# U_I_Meter_TOP.net
KiCad netlist of a schematic drawn in Altium Designer
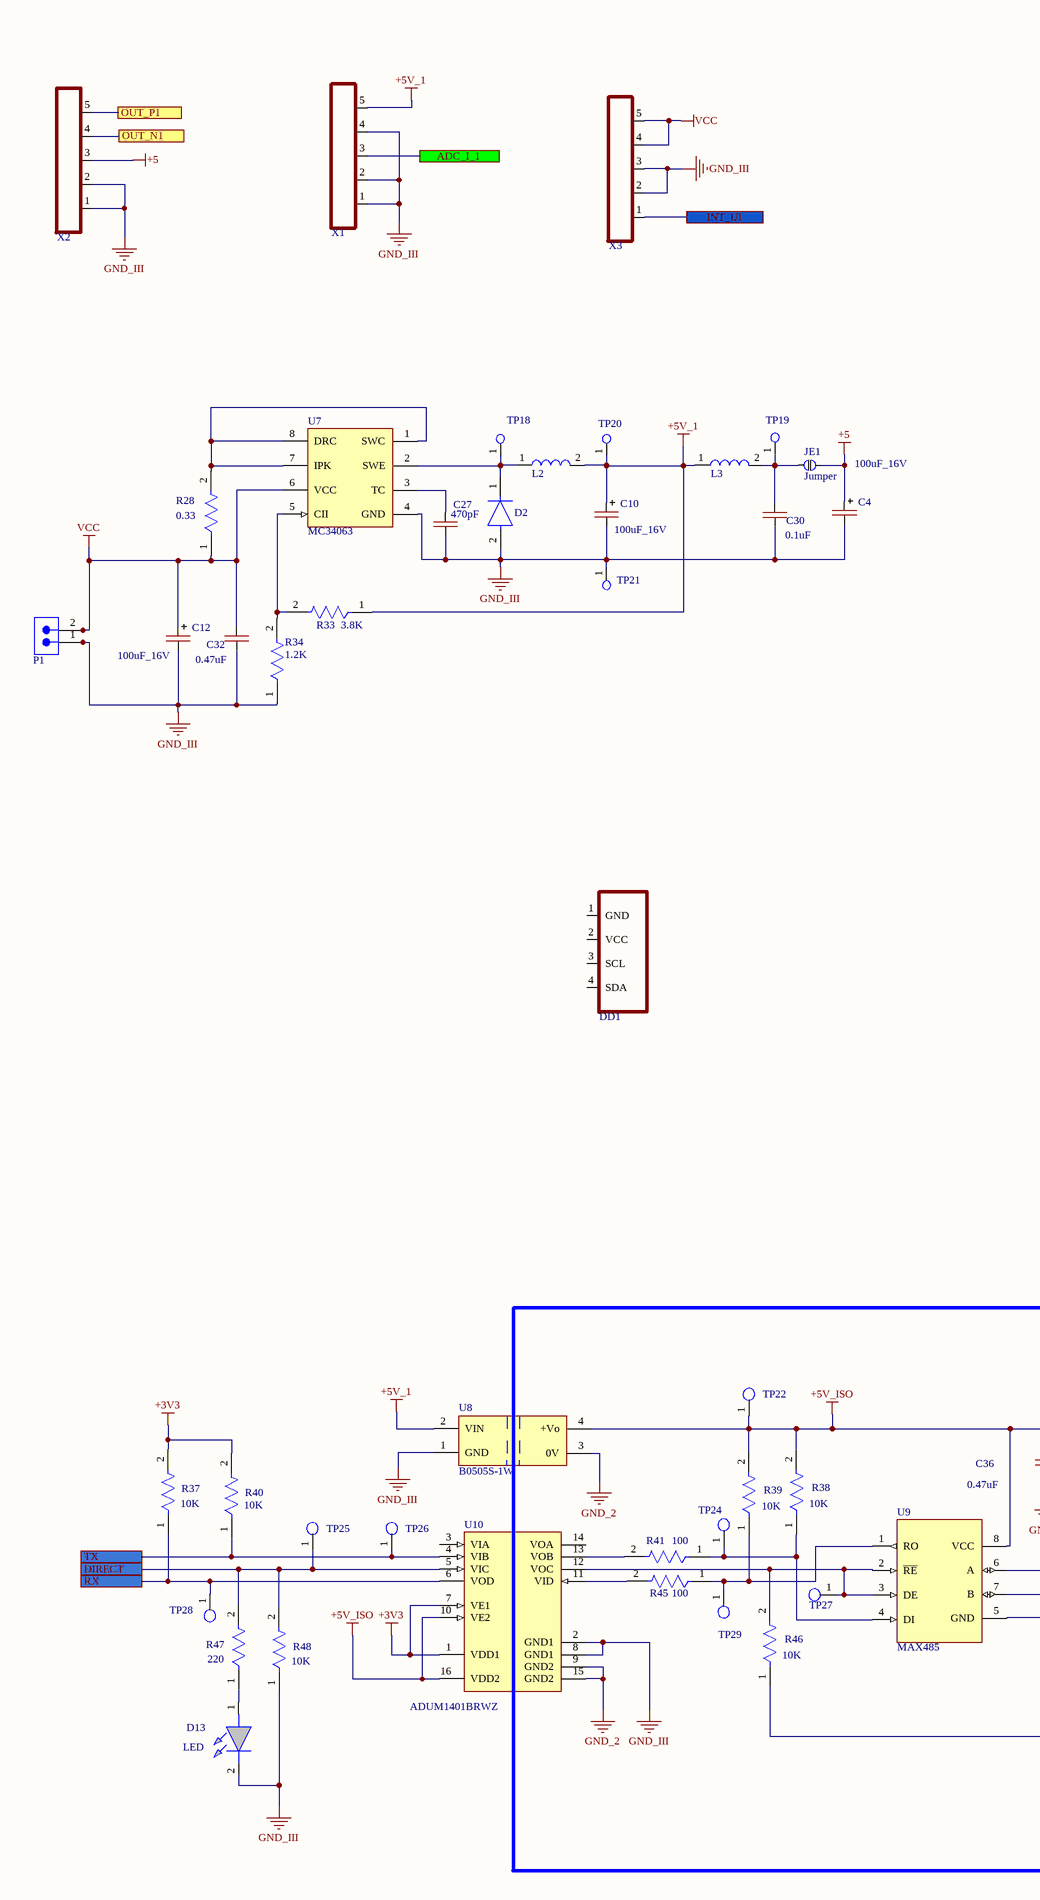
[diagram p0: U_I_Meter_TOP.SchDoc, left]
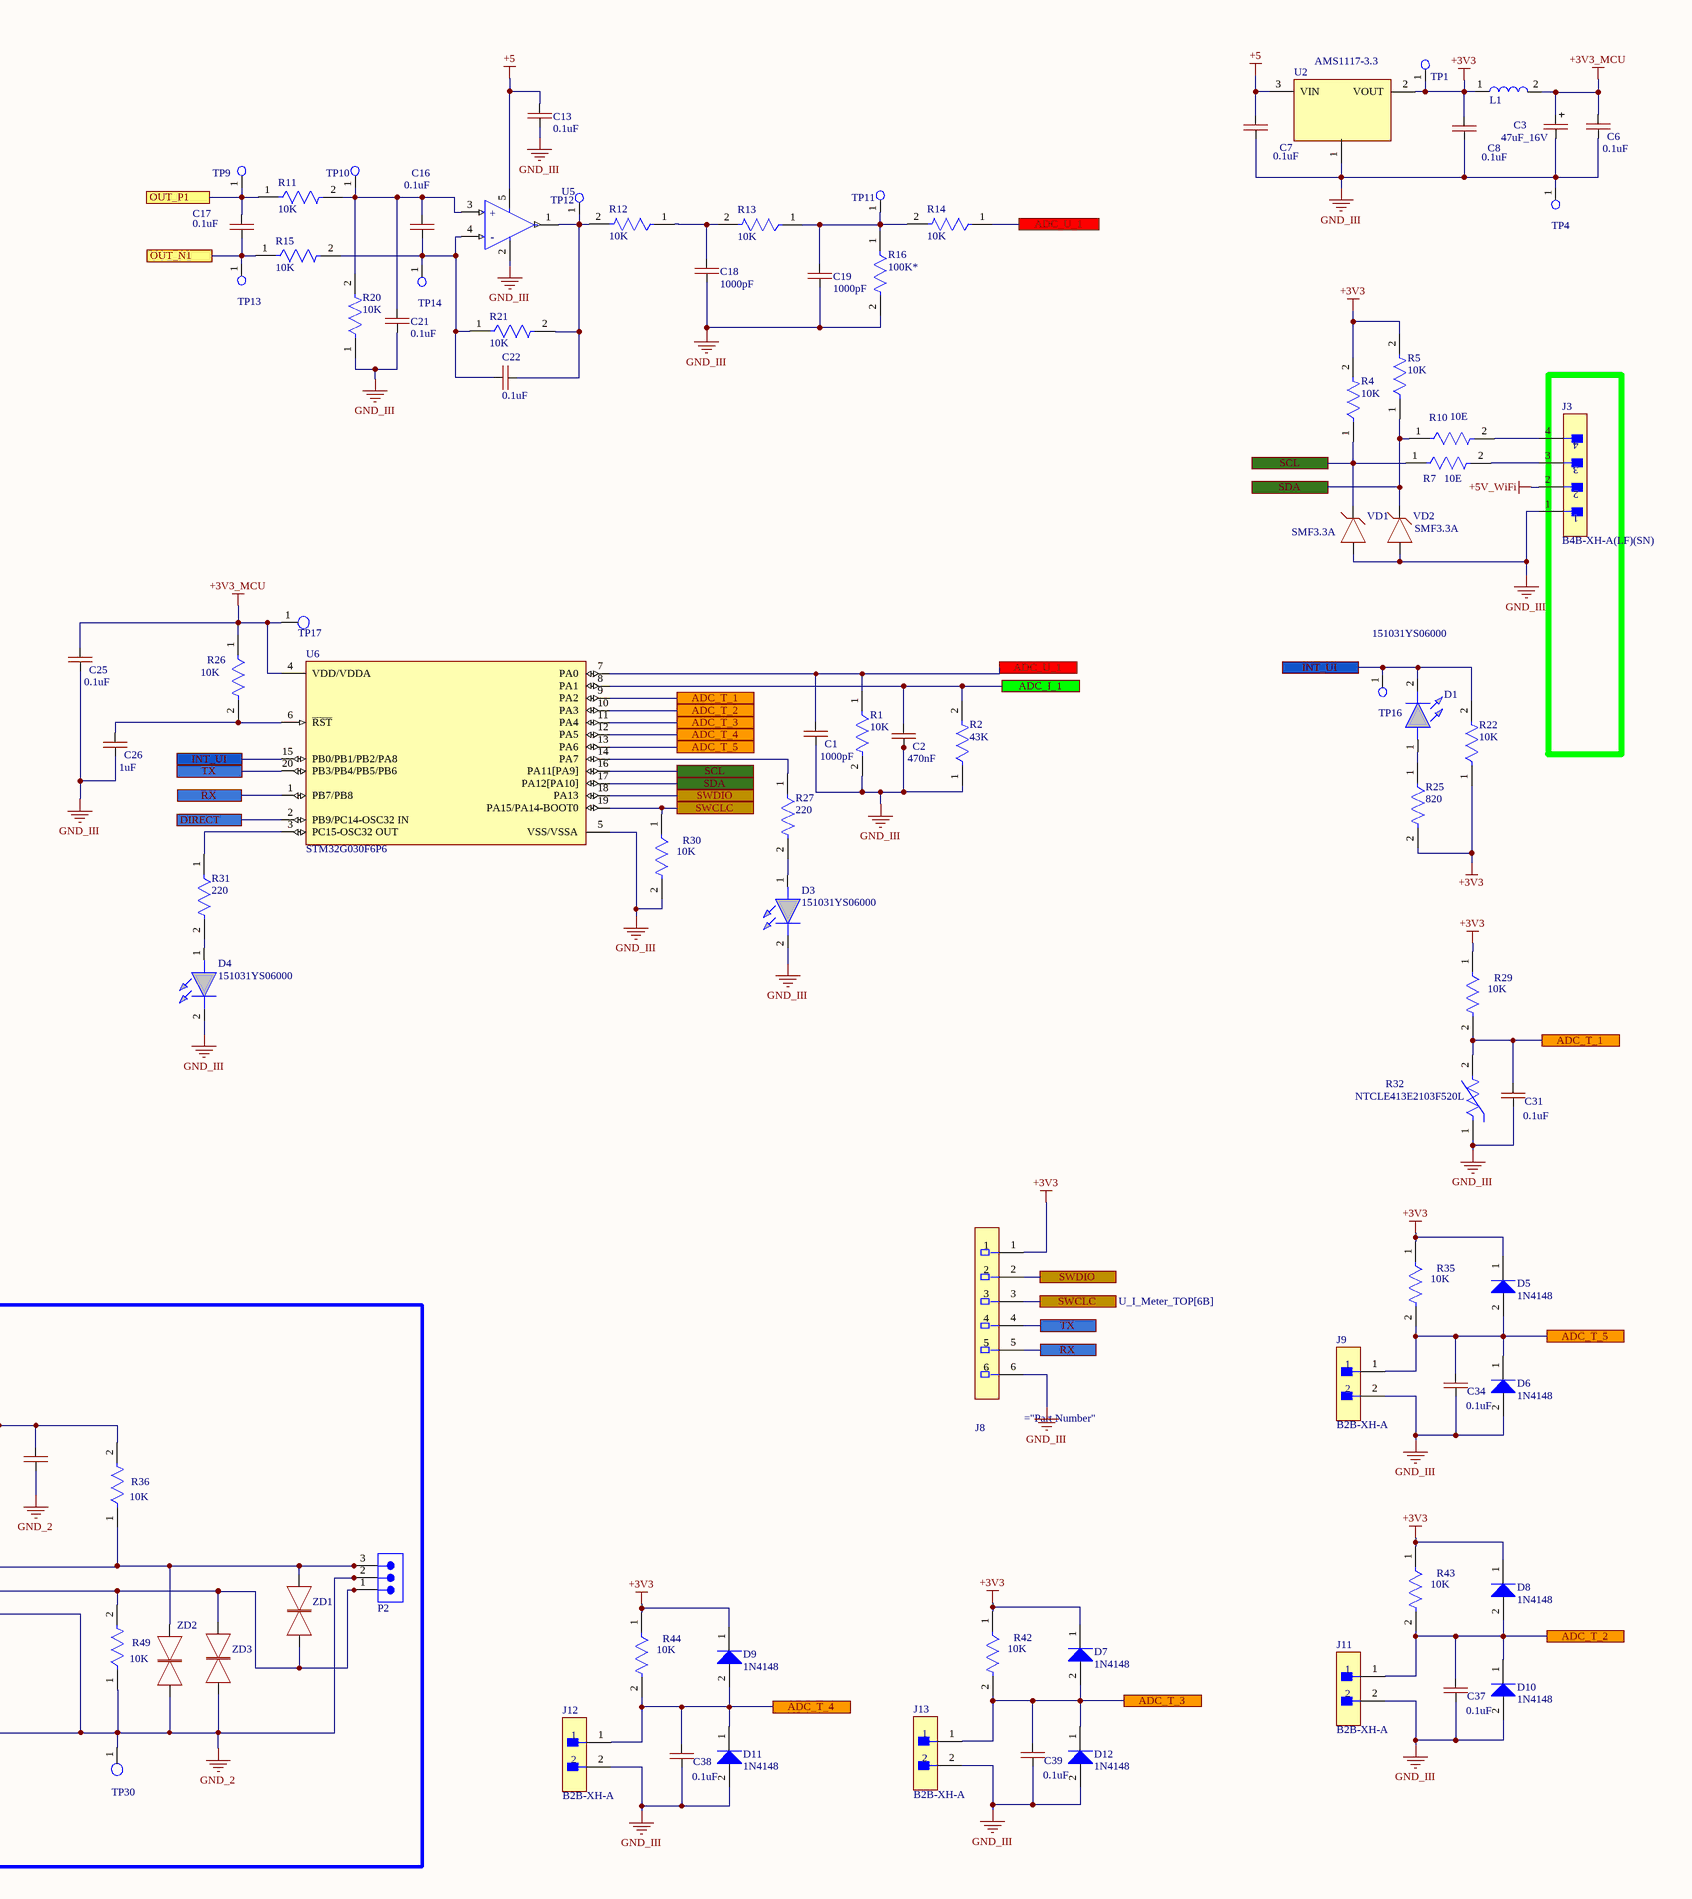
[diagram p1: U_I_Meter_TOP.SchDoc, right]

(export (version "E")
  (design (tool "Eeschema 10.0.6"))
  (components
    (comp (ref "C1")
      (value "1000pF")
      (footprint "CAP-0805")
      (libsource (lib "PASSIVE_COMPONENTS") (part "CAP-NON-POLAR"))
    )
    (comp (ref "C2")
      (value "470nF")
      (footprint "CAP-0805")
      (libsource (lib "PASSIVE_COMPONENTS") (part "CAP-NON-POLAR"))
    )
    (comp (ref "C3")
      (value "47uF_16V")
      (footprint "CAP-TAN-D")
      (libsource (lib "PASSIVE_COMPONENTS") (part "CAP-POLAR"))
    )
    (comp (ref "C4")
      (value "100uF_16V")
      (footprint "CAP-TAN-D")
      (libsource (lib "PASSIVE_COMPONENTS") (part "CAP_POL_SMD"))
    )
    (comp (ref "C6")
      (value "0.1uF")
      (footprint "CAP-0805")
      (libsource (lib "PASSIVE_COMPONENTS") (part "CAP-NON-POLAR"))
    )
    (comp (ref "C7")
      (value "0.1uF")
      (footprint "CAP-0805")
      (libsource (lib "PASSIVE_COMPONENTS") (part "CAP-NON-POLAR"))
    )
    (comp (ref "C8")
      (value "0.1uF")
      (footprint "CAP-0805")
      (libsource (lib "PASSIVE_COMPONENTS") (part "CAP-NON-POLAR"))
    )
    (comp (ref "C10")
      (value "100uF_16V")
      (footprint "CAP-TAN-D")
      (libsource (lib "PASSIVE_COMPONENTS") (part "CAP_POL_SMD"))
    )
    (comp (ref "C12")
      (value "100uF_16V")
      (footprint "CAP-TAN-D")
      (libsource (lib "PASSIVE_COMPONENTS") (part "CAP_POL_SMD"))
    )
    (comp (ref "C13")
      (value "0.1uF")
      (footprint "CAP-0805")
      (libsource (lib "PASSIVE_COMPONENTS") (part "CAP-NON-POLAR"))
    )
    (comp (ref "C16")
      (value "0.1uF")
      (footprint "CAP-0805")
      (libsource (lib "PASSIVE_COMPONENTS") (part "CAP-NON-POLAR"))
    )
    (comp (ref "C17")
      (value "0.1uF")
      (footprint "CAP-0805")
      (libsource (lib "PASSIVE_COMPONENTS") (part "CAP-NON-POLAR"))
    )
    (comp (ref "C18")
      (value "1000pF")
      (footprint "CAP-0805")
      (libsource (lib "PASSIVE_COMPONENTS") (part "CAP-NON-POLAR"))
    )
    (comp (ref "C19")
      (value "1000pF")
      (footprint "CAP-0805")
      (libsource (lib "PASSIVE_COMPONENTS") (part "CAP-NON-POLAR"))
    )
    (comp (ref "C21")
      (value "0.1uF")
      (footprint "CAP-0805")
      (libsource (lib "PASSIVE_COMPONENTS") (part "CAP-NON-POLAR"))
    )
    (comp (ref "C22")
      (value "0.1uF")
      (footprint "CAP-0805")
      (libsource (lib "PASSIVE_COMPONENTS") (part "CAP-NON-POLAR"))
    )
    (comp (ref "C25")
      (value "0.1uF")
      (footprint "CAP-0805")
      (libsource (lib "PASSIVE_COMPONENTS") (part "CAP-NON-POLAR"))
    )
    (comp (ref "C26")
      (value "1uF")
      (footprint "CAP-0805")
      (libsource (lib "PASSIVE_COMPONENTS") (part "CAP-NON-POLAR"))
    )
    (comp (ref "C27")
      (value "470pF")
      (footprint "CAP-0805")
      (libsource (lib "PASSIVE_COMPONENTS") (part "CAP-NON-POLAR"))
    )
    (comp (ref "C30")
      (value "0.1uF")
      (footprint "CAP-0805")
      (libsource (lib "PASSIVE_COMPONENTS") (part "CAP-NON-POLAR"))
    )
    (comp (ref "C31")
      (value "0.1uF")
      (footprint "CAP-0805")
      (libsource (lib "PASSIVE_COMPONENTS") (part "CAP-NON-POLAR"))
    )
    (comp (ref "C32")
      (value "0.47uF")
      (footprint "CAP-0805")
      (libsource (lib "PASSIVE_COMPONENTS") (part "CAP-NON-POLAR"))
    )
    (comp (ref "C34")
      (value "0.1uF")
      (footprint "CAP-0805")
      (libsource (lib "PASSIVE_COMPONENTS") (part "CAP-NON-POLAR"))
    )
    (comp (ref "C36")
      (value "0.47uF")
      (footprint "CAP-0805")
      (libsource (lib "PASSIVE_COMPONENTS") (part "CAP-NON-POLAR"))
    )
    (comp (ref "C37")
      (value "0.1uF")
      (footprint "CAP-0805")
      (libsource (lib "PASSIVE_COMPONENTS") (part "CAP-NON-POLAR"))
    )
    (comp (ref "C38")
      (value "0.1uF")
      (footprint "CAP-0805")
      (libsource (lib "PASSIVE_COMPONENTS") (part "CAP-NON-POLAR"))
    )
    (comp (ref "C39")
      (value "0.1uF")
      (footprint "CAP-0805")
      (libsource (lib "PASSIVE_COMPONENTS") (part "CAP-NON-POLAR"))
    )
    (comp (ref "D1")
      (value "151031YS06000")
      (footprint "LED_3mm_BLUE")
      (description "WURTH ELEKTRONIK - 151031YS06000 - LED, Yellow, Through Hole, T-1 (3mm), 30 mA, 2 V, 590 nm")
      (fields (field (name "MOUSER PART NUMBER") "710-151031YS06000"))
      (libsource (lib "Optic-LED") (part "LED"))
    )
    (comp (ref "D2") (value "US1G") (footprint "US1G_SMA") (libsource (lib "Diodes") (part "US1G")))
    (comp (ref "D3")
      (value "151031YS06000")
      (footprint "LED_3mm_GREEN")
      (description "WURTH ELEKTRONIK - 151031YS06000 - LED, Yellow, Through Hole, T-1 (3mm), 30 mA, 2 V, 590 nm")
      (fields (field (name "MOUSER PART NUMBER") "710-151031YS06000"))
      (libsource (lib "Optic-LED") (part "LED"))
    )
    (comp (ref "D4")
      (value "151031YS06000")
      (footprint "LED_3mm_RED")
      (description "WURTH ELEKTRONIK - 151031YS06000 - LED, Yellow, Through Hole, T-1 (3mm), 30 mA, 2 V, 590 nm")
      (fields (field (name "MOUSER PART NUMBER") "710-151031YS06000"))
      (libsource (lib "Optic-LED") (part "LED"))
    )
    (comp (ref "D5")
      (value "1N4148")
      (footprint "DIOD-SOD123-2_V")
      (libsource (lib "Diodes") (part "1N4148"))
    )
    (comp (ref "D6")
      (value "1N4148")
      (footprint "DIOD-SOD123-2_V")
      (libsource (lib "Diodes") (part "1N4148"))
    )
    (comp (ref "D7")
      (value "1N4148")
      (footprint "DIOD-SOD123-2_V")
      (libsource (lib "Diodes") (part "1N4148"))
    )
    (comp (ref "D8")
      (value "1N4148")
      (footprint "DIOD-SOD123-2_V")
      (libsource (lib "Diodes") (part "1N4148"))
    )
    (comp (ref "D9")
      (value "1N4148")
      (footprint "DIOD-SOD123-2_V")
      (libsource (lib "Diodes") (part "1N4148"))
    )
    (comp (ref "D10")
      (value "1N4148")
      (footprint "DIOD-SOD123-2_V")
      (libsource (lib "Diodes") (part "1N4148"))
    )
    (comp (ref "D11")
      (value "1N4148")
      (footprint "DIOD-SOD123-2_V")
      (libsource (lib "Diodes") (part "1N4148"))
    )
    (comp (ref "D12")
      (value "1N4148")
      (footprint "DIOD-SOD123-2_V")
      (libsource (lib "Diodes") (part "1N4148"))
    )
    (comp (ref "D13")
      (value "LED")
      (footprint "LED_3mm_BLUE")
      (description "WURTH ELEKTRONIK - 151031YS06000 - LED, Yellow, Through Hole, T-1 (3mm), 30 mA, 2 V, 590 nm")
      (fields
        (field (name "MANUFACTURER_PART_NUMBER") "151031YS06000")
        (field (name "MOUSER PART NUMBER") "710-151031YS06000")
      )
      (libsource (lib "Optic-LED") (part "LED"))
    )
    (comp (ref "DD1")
      (value "OLED_SSD_1306")
      (footprint "OLED_128x64_SSD_1306")
      (libsource (lib "OLED_SSD_1306") (part "OLED_SSD_1306"))
    )
    (comp (ref "J3")
      (value "B4B-XH-A(LF)(SN)")
      (footprint "B4B-XH-A")
      (libsource (lib "Connectors") (part "B4B-XH-A(LF)(SN)"))
    )
    (comp (ref "J8")
      (value "SWR25X-NRTC-S06-ST-BA")
      (footprint "Sullins_SWR25X-NRTC-S06-ST-BA_MFG")
      (libsource (lib "Conn_Sullins_SWR25X-NRTC-S06-ST-BA_eec") (part "SWR25X-NRTC-S06-ST-BA"))
    )
    (comp (ref "J9")
      (value "B2B-XH-A")
      (footprint "B2B-XH-A")
      (libsource (lib "Connectors") (part "B2B-XH-A"))
    )
    (comp (ref "J11")
      (value "B2B-XH-A")
      (footprint "B2B-XH-A")
      (libsource (lib "Connectors") (part "B2B-XH-A"))
    )
    (comp (ref "J12")
      (value "B2B-XH-A")
      (footprint "B2B-XH-A")
      (libsource (lib "Connectors") (part "B2B-XH-A"))
    )
    (comp (ref "J13")
      (value "B2B-XH-A")
      (footprint "B2B-XH-A")
      (libsource (lib "Connectors") (part "B2B-XH-A"))
    )
    (comp (ref "JE1") (value "Jumper") (footprint "JE") (libsource (lib "Connectors") (part "JE")))
    (comp (ref "L1")
      (value "Coil")
      (footprint "Coil_4.5x4.5_mm")
      (libsource (lib "Transformers") (part "Coil"))
    )
    (comp (ref "L2")
      (value "Coil")
      (footprint "Coil_4.5x4.5_mm")
      (libsource (lib "Transformers") (part "Coil"))
    )
    (comp (ref "L3")
      (value "Coil")
      (footprint "Coil_4.5x4.5_mm")
      (libsource (lib "Transformers") (part "Coil"))
    )
    (comp (ref "P1")
      (value "691701530002B")
      (footprint "691701530002B")
      (description "WR-TBL Series 7015B Open Horizontal PCB Header, SMT, pitch 5.08mm, 2p")
      (fields (field (name "MANUFACTURER") "Wurth Elektronik"))
      (libsource (lib "Altium_WR-TBL (rev23d)") (part "691701530002B"))
    )
    (comp (ref "P2")
      (value "691701530003B")
      (footprint "691701530003B")
      (description "WR-TBL Series 7015B Open Horizontal PCB Header, SMT, pitch 5.08mm, 3p")
      (fields (field (name "MANUFACTURER") "Wurth Elektronik"))
      (libsource (lib "Altium_WR-TBL (rev23d)") (part "691701530003B"))
    )
    (comp (ref "R1")
      (value "10K")
      (footprint "RES-0805")
      (libsource (lib "PASSIVE_COMPONENTS") (part "RES-CONST"))
    )
    (comp (ref "R2")
      (value "43K")
      (footprint "RES-0805")
      (libsource (lib "PASSIVE_COMPONENTS") (part "RES-CONST"))
    )
    (comp (ref "R4")
      (value "10K")
      (footprint "RES-0805")
      (libsource (lib "PASSIVE_COMPONENTS") (part "RES-CONST"))
    )
    (comp (ref "R5")
      (value "10K")
      (footprint "RES-0805")
      (libsource (lib "PASSIVE_COMPONENTS") (part "RES-CONST"))
    )
    (comp (ref "R7")
      (value "10E")
      (footprint "RES-0805")
      (libsource (lib "PASSIVE_COMPONENTS") (part "RES-CONST"))
    )
    (comp (ref "R10")
      (value "10E")
      (footprint "RES-0805")
      (libsource (lib "PASSIVE_COMPONENTS") (part "RES-CONST"))
    )
    (comp (ref "R11")
      (value "10K")
      (footprint "RES-0805")
      (libsource (lib "PASSIVE_COMPONENTS") (part "RES-CONST"))
    )
    (comp (ref "R12")
      (value "10K")
      (footprint "RES-0805")
      (libsource (lib "PASSIVE_COMPONENTS") (part "RES-CONST"))
    )
    (comp (ref "R13")
      (value "10K")
      (footprint "RES-0805")
      (libsource (lib "PASSIVE_COMPONENTS") (part "RES-CONST"))
    )
    (comp (ref "R14")
      (value "10K")
      (footprint "RES-0805")
      (libsource (lib "PASSIVE_COMPONENTS") (part "RES-CONST"))
    )
    (comp (ref "R15")
      (value "10K")
      (footprint "RES-0805")
      (libsource (lib "PASSIVE_COMPONENTS") (part "RES-CONST"))
    )
    (comp (ref "R16")
      (value "100K*")
      (footprint "RES-0805")
      (libsource (lib "PASSIVE_COMPONENTS") (part "RES-CONST"))
    )
    (comp (ref "R20")
      (value "10K")
      (footprint "RES-0805")
      (libsource (lib "PASSIVE_COMPONENTS") (part "RES-CONST"))
    )
    (comp (ref "R21")
      (value "10K")
      (footprint "RES-0805")
      (libsource (lib "PASSIVE_COMPONENTS") (part "RES-CONST"))
    )
    (comp (ref "R22")
      (value "10K")
      (footprint "RES-0805")
      (libsource (lib "PASSIVE_COMPONENTS") (part "RES-CONST"))
    )
    (comp (ref "R25")
      (value "820")
      (footprint "RES-0805")
      (description "220")
      (libsource (lib "PASSIVE_COMPONENTS") (part "RES-CONST"))
    )
    (comp (ref "R26")
      (value "10K")
      (footprint "RES-0805")
      (libsource (lib "PASSIVE_COMPONENTS") (part "RES-CONST"))
    )
    (comp (ref "R27")
      (value "220")
      (footprint "RES-0805")
      (libsource (lib "PASSIVE_COMPONENTS") (part "RES-CONST"))
    )
    (comp (ref "R28")
      (value "0.33")
      (footprint "RES-1206")
      (libsource (lib "PASSIVE_COMPONENTS") (part "RES-CONST"))
    )
    (comp (ref "R29")
      (value "10K")
      (footprint "RES-0805")
      (libsource (lib "PASSIVE_COMPONENTS") (part "RES-CONST"))
    )
    (comp (ref "R30")
      (value "10K")
      (footprint "RES-0805")
      (libsource (lib "PASSIVE_COMPONENTS") (part "RES-CONST"))
    )
    (comp (ref "R31")
      (value "220")
      (footprint "RES-0805")
      (libsource (lib "PASSIVE_COMPONENTS") (part "RES-CONST"))
    )
    (comp (ref "R32")
      (value "NTCLE413E2103F520L")
      (footprint "FP-NTCLE413E2103F520L-MFG")
      (description "THERMISTOR NTC 10KOHM 3435K BEAD")
      (fields (field (name "TOLERANCE") "1%"))
      (libsource (lib "Altium Content Vault") (part "3b148a6ebabc5fb4d708a66c052d352"))
    )
    (comp (ref "R33")
      (value "3.8K")
      (footprint "RES-0805")
      (description "10K")
      (libsource (lib "PASSIVE_COMPONENTS") (part "RES-CONST"))
    )
    (comp (ref "R34")
      (value "1.2K")
      (footprint "RES-0805")
      (libsource (lib "PASSIVE_COMPONENTS") (part "RES-CONST"))
    )
    (comp (ref "R35")
      (value "10K")
      (footprint "RES-0805")
      (libsource (lib "PASSIVE_COMPONENTS") (part "RES-CONST"))
    )
    (comp (ref "R36")
      (value "10K")
      (footprint "RES-0805")
      (libsource (lib "PASSIVE_COMPONENTS") (part "RES-CONST"))
    )
    (comp (ref "R37")
      (value "10K")
      (footprint "RES-0805")
      (libsource (lib "PASSIVE_COMPONENTS") (part "RES-CONST"))
    )
    (comp (ref "R38")
      (value "10K")
      (footprint "RES-0805")
      (libsource (lib "PASSIVE_COMPONENTS") (part "RES-CONST"))
    )
    (comp (ref "R39")
      (value "10K")
      (footprint "RES-0805")
      (libsource (lib "PASSIVE_COMPONENTS") (part "RES-CONST"))
    )
    (comp (ref "R40")
      (value "10K")
      (footprint "RES-0805")
      (libsource (lib "PASSIVE_COMPONENTS") (part "RES-CONST"))
    )
    (comp (ref "R41")
      (value "100")
      (footprint "RES-0805")
      (libsource (lib "PASSIVE_COMPONENTS") (part "RES-CONST"))
    )
    (comp (ref "R42")
      (value "10K")
      (footprint "RES-0805")
      (libsource (lib "PASSIVE_COMPONENTS") (part "RES-CONST"))
    )
    (comp (ref "R43")
      (value "10K")
      (footprint "RES-0805")
      (libsource (lib "PASSIVE_COMPONENTS") (part "RES-CONST"))
    )
    (comp (ref "R44")
      (value "10K")
      (footprint "RES-0805")
      (libsource (lib "PASSIVE_COMPONENTS") (part "RES-CONST"))
    )
    (comp (ref "R45")
      (value "100")
      (footprint "RES-0805")
      (libsource (lib "PASSIVE_COMPONENTS") (part "RES-CONST"))
    )
    (comp (ref "R46")
      (value "10K")
      (footprint "RES-0805")
      (libsource (lib "PASSIVE_COMPONENTS") (part "RES-CONST"))
    )
    (comp (ref "R47")
      (value "220")
      (footprint "RES-0805")
      (libsource (lib "PASSIVE_COMPONENTS") (part "RES-CONST"))
    )
    (comp (ref "R48")
      (value "10K")
      (footprint "RES-0805")
      (libsource (lib "PASSIVE_COMPONENTS") (part "RES-CONST"))
    )
    (comp (ref "R49")
      (value "10K")
      (footprint "RES-0805")
      (libsource (lib "PASSIVE_COMPONENTS") (part "RES-CONST"))
    )
    (comp (ref "TP1")
      (value "Test_Point_PCB")
      (footprint "Test_Point")
      (description "Test_Point")
      (libsource (lib "Connectors") (part "TP_PCB?"))
    )
    (comp (ref "TP4")
      (value "Test_Point_PCB")
      (footprint "Pin_Test_Point(Pink)")
      (description "Test_Point")
      (libsource (lib "Connectors") (part "TP_PCB?"))
    )
    (comp (ref "TP9")
      (value "Test_Point_PCB")
      (footprint "Test_Point")
      (description "Test_Point")
      (libsource (lib "Connectors") (part "TP_PCB?"))
    )
    (comp (ref "TP10")
      (value "Test_Point_PCB")
      (footprint "Test_Point")
      (description "Test_Point")
      (libsource (lib "Connectors") (part "TP_PCB?"))
    )
    (comp (ref "TP11")
      (value "Test_Point_PCB")
      (footprint "Test_Point")
      (description "Test_Point")
      (libsource (lib "Connectors") (part "TP_PCB?"))
    )
    (comp (ref "TP12")
      (value "Test_Point_PCB")
      (footprint "Test_Point")
      (description "Test_Point")
      (libsource (lib "Connectors") (part "TP_PCB?"))
    )
    (comp (ref "TP13")
      (value "Test_Point_PCB")
      (footprint "Test_Point")
      (description "Test_Point")
      (libsource (lib "Connectors") (part "TP_PCB?"))
    )
    (comp (ref "TP14")
      (value "Test_Point_PCB")
      (footprint "Test_Point")
      (description "Test_Point")
      (libsource (lib "Connectors") (part "TP_PCB?"))
    )
    (comp (ref "TP16")
      (value "Test_Point_PCB")
      (footprint "Test_Point")
      (description "Test_Point")
      (libsource (lib "Connectors") (part "TP_PCB?"))
    )
    (comp (ref "TP17")
      (value "~")
      (footprint "Test_Point")
      (description "Test_Point")
      (libsource (lib "") (part "TP_PCB?_1"))
    )
    (comp (ref "TP18")
      (value "Test_Point_PCB")
      (footprint "Test_Point")
      (description "Test_Point")
      (libsource (lib "Connectors") (part "TP_PCB?"))
    )
    (comp (ref "TP19")
      (value "Test_Point_PCB")
      (footprint "Test_Point")
      (description "Test_Point")
      (libsource (lib "Connectors") (part "TP_PCB?"))
    )
    (comp (ref "TP20")
      (value "Test_Point_PCB")
      (footprint "Test_Point")
      (description "Test_Point")
      (libsource (lib "Connectors") (part "TP_PCB?"))
    )
    (comp (ref "TP21")
      (value "Test_Point_PCB")
      (footprint "Pin_Test_Point(Orange)")
      (description "Test_Point")
      (libsource (lib "Connectors") (part "TP_PCB?"))
    )
    (comp (ref "TP22")
      (value "Test_Point_PCB")
      (footprint "Test_Point")
      (description "Test_Point")
      (libsource (lib "Test_Point") (part "TP_PCB?"))
    )
    (comp (ref "TP24")
      (value "Test_Point_PCB")
      (footprint "Test_Point")
      (description "Test_Point")
      (libsource (lib "Test_Point") (part "TP_PCB?"))
    )
    (comp (ref "TP25")
      (value "Test_Point_PCB")
      (footprint "Test_Point")
      (description "Test_Point")
      (libsource (lib "Test_Point") (part "TP_PCB?"))
    )
    (comp (ref "TP26")
      (value "Test_Point_PCB")
      (footprint "Test_Point")
      (description "Test_Point")
      (libsource (lib "Test_Point") (part "TP_PCB?"))
    )
    (comp (ref "TP27")
      (value "Test_Point_PCB")
      (footprint "Test_Point")
      (description "Test_Point")
      (libsource (lib "Test_Point") (part "TP_PCB?"))
    )
    (comp (ref "TP28")
      (value "Test_Point_PCB")
      (footprint "Test_Point")
      (description "Test_Point")
      (libsource (lib "Test_Point") (part "TP_PCB?"))
    )
    (comp (ref "TP29")
      (value "~")
      (footprint "Test_Point")
      (description "Test_Point")
      (libsource (lib "") (part "TP_PCB?_1"))
    )
    (comp (ref "TP30")
      (value "Test_Point_PCB")
      (footprint "Test_Point")
      (description "Test_Point")
      (libsource (lib "Test_Point") (part "TP_PCB?"))
    )
    (comp (ref "U2")
      (value "AMS1117-3.3")
      (footprint "SOT-223")
      (libsource (lib "Integrated_Circuts") (part "AMS1117"))
    )
    (comp (ref "U5")
      (value "~")
      (footprint "SOT-23-5")
      (description "IC OPAMP GP 1 CIRCUIT SOT23-5")
      (fields (field (name "VOLTAGE") "6V"))
      (libsource (lib "Integrated_Circuts") (part "MCP6001T"))
    )
    (comp (ref "U6")
      (value "STM32G030F6P6")
      (footprint "FP-TSSOP20-YA-IPC_A")
      (description "SOIC-20")
      (libsource (lib "Integrated_Circuts") (part "STM32G030F6P6"))
    )
    (comp (ref "U7")
      (value "MC34063")
      (footprint "SOIC-8_M")
      (libsource (lib "Integrated_Circuts") (part "MC34063"))
    )
    (comp (ref "U8")
      (value "B0505S-1W")
      (footprint "B0505S-1W")
      (libsource (lib "Integrated_Circuts") (part "B0505S-1W"))
    )
    (comp (ref "U9")
      (value "MAX485")
      (footprint "SOIC-8-MFG")
      (libsource (lib "Integrated_Circuts") (part "MAX485"))
    )
    (comp (ref "U10")
      (value "ADUM1401BRWZ")
      (footprint "ADI-RW-16_M")
      (fields (field (name "MANUFACTURER") "Analog Devices"))
      (libsource (lib "Altium Content Vault") (part "ADI-ADUMX4X1-16"))
    )
    (comp (ref "VD1")
      (value "SMF3.3A")
      (footprint "SMF3.3A")
      (libsource (lib "Diodes") (part "ESD_Unidirect"))
    )
    (comp (ref "VD2")
      (value "SMF3.3A")
      (footprint "SMF3.3A")
      (libsource (lib "Diodes") (part "ESD_Unidirect"))
    )
    (comp (ref "X1")
      (value "CONN-5-PIN")
      (footprint "CONN-PLS-5-2.54_2")
      (libsource (lib "PLS-5__") (part "CONN-5-PIN"))
    )
    (comp (ref "X2")
      (value "CONN-5-PIN")
      (footprint "CONN-PLS-5-2.54_2")
      (libsource (lib "PLS-5__") (part "CONN-5-PIN"))
    )
    (comp (ref "X3")
      (value "CONN-5-PIN")
      (footprint "CONN-PLS-5-2.54_2")
      (libsource (lib "PLS-5__") (part "CONN-5-PIN"))
    )
    (comp (ref "ZD1")
      (value "P6SMB16CA")
      (footprint "DO-214AA")
      (libsource (lib "P6SMB16CA") (part "P6SMB16CA"))
    )
    (comp (ref "ZD2")
      (value "P6SMB16CA")
      (footprint "DO-214AA")
      (libsource (lib "P6SMB16CA") (part "P6SMB16CA"))
    )
    (comp (ref "ZD3")
      (value "P6SMB16CA")
      (footprint "DO-214AA")
      (libsource (lib "P6SMB16CA") (part "P6SMB16CA"))
    )
  )
  (nets
    (net (code "1") (name "+3V3") (class "Default")
      (node (ref "C8") (pin "2") (pinfunction "2_2") (pintype "passive"))
      (node (ref "D5") (pin "1") (pinfunction "K_1") (pintype "passive"))
      (node (ref "D7") (pin "1") (pinfunction "K_1") (pintype "passive"))
      (node (ref "D8") (pin "1") (pinfunction "K_1") (pintype "passive"))
      (node (ref "D9") (pin "1") (pinfunction "K_1") (pintype "passive"))
      (node (ref "J8") (pin "1") (pinfunction "1_1") (pintype "passive"))
      (node (ref "L1") (pin "1") (pinfunction "1_1") (pintype "passive"))
      (node (ref "R22") (pin "1") (pinfunction "1_1") (pintype "passive"))
      (node (ref "R25") (pin "2") (pinfunction "2_2") (pintype "passive"))
      (node (ref "R29") (pin "1") (pinfunction "1_1") (pintype "passive"))
      (node (ref "R35") (pin "1") (pinfunction "1_1") (pintype "passive"))
      (node (ref "R37") (pin "2") (pinfunction "2_2") (pintype "passive"))
      (node (ref "R4") (pin "2") (pinfunction "2_2") (pintype "passive"))
      (node (ref "R40") (pin "2") (pinfunction "2_2") (pintype "passive"))
      (node (ref "R42") (pin "1") (pinfunction "1_1") (pintype "passive"))
      (node (ref "R43") (pin "1") (pinfunction "1_1") (pintype "passive"))
      (node (ref "R44") (pin "1") (pinfunction "1_1") (pintype "passive"))
      (node (ref "R5") (pin "2") (pinfunction "2_2") (pintype "passive"))
      (node (ref "TP1") (pin "1") (pinfunction "G9_1") (pintype "passive"))
      (node (ref "U10") (pin "1") (pinfunction "VDD1_1") (pintype "power_in"))
      (node (ref "U10") (pin "7") (pinfunction "VE1_7") (pintype "input"))
      (node (ref "U2") (pin "2") (pinfunction "VOUT_2") (pintype "passive"))
    )
    (net (code "2") (name "+3V3_MCU") (class "Default")
      (node (ref "C25") (pin "2") (pinfunction "2_2") (pintype "passive"))
      (node (ref "C3") (pin "1") (pinfunction "+_1") (pintype "passive"))
      (node (ref "C6") (pin "2") (pinfunction "2_2") (pintype "passive"))
      (node (ref "L1") (pin "2") (pinfunction "2_2") (pintype "passive"))
      (node (ref "R26") (pin "1") (pinfunction "1_1") (pintype "passive"))
      (node (ref "TP17") (pin "1") (pinfunction "G9_1") (pintype "passive"))
      (node (ref "U6") (pin "4") (pinfunction "VDD/VDDA_4") (pintype "power_in"))
    )
    (net (code "3") (name "+5") (class "Default")
      (node (ref "C13") (pin "2") (pinfunction "2_2") (pintype "passive"))
      (node (ref "C4") (pin "1") (pinfunction "+_1") (pintype "passive"))
      (node (ref "C7") (pin "2") (pinfunction "2_2") (pintype "passive"))
      (node (ref "JE1") (pin "1") (pinfunction "1_1") (pintype "passive"))
      (node (ref "U2") (pin "3") (pinfunction "VIN_3") (pintype "power_in"))
      (node (ref "U5") (pin "5") (pinfunction "VDD_5") (pintype "power_in"))
      (node (ref "X2") (pin "3") (pinfunction "3_3") (pintype "passive"))
    )
    (net (code "4") (name "+5V_1") (class "Default")
      (node (ref "C10") (pin "1") (pinfunction "+_1") (pintype "passive"))
      (node (ref "L2") (pin "2") (pinfunction "2_2") (pintype "passive"))
      (node (ref "L3") (pin "1") (pinfunction "1_1") (pintype "passive"))
      (node (ref "R33") (pin "1") (pinfunction "1_1") (pintype "passive"))
      (node (ref "TP20") (pin "1") (pinfunction "G9_1") (pintype "passive"))
      (node (ref "U8") (pin "2") (pinfunction "VIN_2") (pintype "power_in"))
      (node (ref "X1") (pin "5") (pinfunction "5_5") (pintype "passive"))
    )
    (net (code "5") (name "+5V_ISO") (class "Default")
      (node (ref "C36") (pin "1") (pinfunction "1_1") (pintype "passive"))
      (node (ref "R36") (pin "2") (pinfunction "2_2") (pintype "passive"))
      (node (ref "R38") (pin "2") (pinfunction "2_2") (pintype "passive"))
      (node (ref "R39") (pin "2") (pinfunction "2_2") (pintype "passive"))
      (node (ref "TP22") (pin "1") (pinfunction "G9_1") (pintype "passive"))
      (node (ref "U10") (pin "10") (pinfunction "VE2_10") (pintype "input"))
      (node (ref "U10") (pin "16") (pinfunction "VDD2_16") (pintype "power_in"))
      (node (ref "U8") (pin "4") (pinfunction "+Vo_4") (pintype "power_in"))
      (node (ref "U9") (pin "8") (pinfunction "VCC_8") (pintype "power_in"))
    )
    (net (code "6") (name "+5V_WiFi") (class "Default")
      (node (ref "J3") (pin "2") (pinfunction "2_2") (pintype "passive"))
    )
    (net (code "7") (name "/ADC_I_1") (class "Default")
      (node (ref "C2") (pin "2") (pinfunction "2_2") (pintype "passive"))
      (node (ref "R2") (pin "2") (pinfunction "2_2") (pintype "passive"))
      (node (ref "U6") (pin "8") (pinfunction "PA1_8") (pintype "bidirectional"))
      (node (ref "X1") (pin "3") (pinfunction "3_3") (pintype "passive"))
    )
    (net (code "8") (name "/ADC_T_1") (class "Default")
      (node (ref "C31") (pin "2") (pinfunction "2_2") (pintype "passive"))
      (node (ref "R29") (pin "2") (pinfunction "2_2") (pintype "passive"))
      (node (ref "R32") (pin "2") (pinfunction "2_2") (pintype "passive"))
      (node (ref "U6") (pin "9") (pinfunction "PA2_9") (pintype "bidirectional"))
    )
    (net (code "9") (name "/ADC_T_2") (class "Default")
      (node (ref "C37") (pin "2") (pinfunction "2_2") (pintype "passive"))
      (node (ref "D10") (pin "1") (pinfunction "K_1") (pintype "passive"))
      (node (ref "D8") (pin "2") (pinfunction "A_2") (pintype "passive"))
      (node (ref "J11") (pin "1") (pinfunction "1_1") (pintype "passive"))
      (node (ref "R43") (pin "2") (pinfunction "2_2") (pintype "passive"))
      (node (ref "U6") (pin "10") (pinfunction "PA3_10") (pintype "bidirectional"))
    )
    (net (code "10") (name "/ADC_T_3") (class "Default")
      (node (ref "C39") (pin "2") (pinfunction "2_2") (pintype "passive"))
      (node (ref "D12") (pin "1") (pinfunction "K_1") (pintype "passive"))
      (node (ref "D7") (pin "2") (pinfunction "A_2") (pintype "passive"))
      (node (ref "J13") (pin "1") (pinfunction "1_1") (pintype "passive"))
      (node (ref "R42") (pin "2") (pinfunction "2_2") (pintype "passive"))
      (node (ref "U6") (pin "11") (pinfunction "PA4_11") (pintype "bidirectional"))
    )
    (net (code "11") (name "/ADC_T_4") (class "Default")
      (node (ref "C38") (pin "2") (pinfunction "2_2") (pintype "passive"))
      (node (ref "D11") (pin "1") (pinfunction "K_1") (pintype "passive"))
      (node (ref "D9") (pin "2") (pinfunction "A_2") (pintype "passive"))
      (node (ref "J12") (pin "1") (pinfunction "1_1") (pintype "passive"))
      (node (ref "R44") (pin "2") (pinfunction "2_2") (pintype "passive"))
      (node (ref "U6") (pin "12") (pinfunction "PA5_12") (pintype "bidirectional"))
    )
    (net (code "12") (name "/ADC_T_5") (class "Default")
      (node (ref "C34") (pin "2") (pinfunction "2_2") (pintype "passive"))
      (node (ref "D5") (pin "2") (pinfunction "A_2") (pintype "passive"))
      (node (ref "D6") (pin "1") (pinfunction "K_1") (pintype "passive"))
      (node (ref "J9") (pin "1") (pinfunction "1_1") (pintype "passive"))
      (node (ref "R35") (pin "2") (pinfunction "2_2") (pintype "passive"))
      (node (ref "U6") (pin "13") (pinfunction "PA6_13") (pintype "bidirectional"))
    )
    (net (code "13") (name "/ADC_U_1") (class "Default")
      (node (ref "C1") (pin "2") (pinfunction "2_2") (pintype "passive"))
      (node (ref "R1") (pin "1") (pinfunction "1_1") (pintype "passive"))
      (node (ref "R14") (pin "1") (pinfunction "1_1") (pintype "passive"))
      (node (ref "U6") (pin "7") (pinfunction "PA0_7") (pintype "bidirectional"))
    )
    (net (code "14") (name "/DIRECT") (class "Default")
      (node (ref "R47") (pin "2") (pinfunction "2_2") (pintype "passive"))
      (node (ref "R48") (pin "2") (pinfunction "2_2") (pintype "passive"))
      (node (ref "TP25") (pin "1") (pinfunction "G9_1") (pintype "passive"))
      (node (ref "U10") (pin "5") (pinfunction "VIC_5") (pintype "input"))
      (node (ref "U6") (pin "2") (pinfunction "PB9/PC14-OSC32_IN_2") (pintype "bidirectional"))
    )
    (net (code "15") (name "/INT_UI") (class "Default")
      (node (ref "D1") (pin "2") (pinfunction "K_2") (pintype "passive"))
      (node (ref "R22") (pin "2") (pinfunction "2_2") (pintype "passive"))
      (node (ref "TP16") (pin "1") (pinfunction "G9_1") (pintype "passive"))
      (node (ref "U6") (pin "15") (pinfunction "PB0/PB1/PB2/PA8_15") (pintype "bidirectional"))
      (node (ref "X3") (pin "1") (pinfunction "1_1") (pintype "passive"))
    )
    (net (code "16") (name "/OUT_N1") (class "Default")
      (node (ref "C17") (pin "1") (pinfunction "1_1") (pintype "passive"))
      (node (ref "R15") (pin "1") (pinfunction "1_1") (pintype "passive"))
      (node (ref "TP13") (pin "1") (pinfunction "G9_1") (pintype "passive"))
      (node (ref "X2") (pin "4") (pinfunction "4_4") (pintype "passive"))
    )
    (net (code "17") (name "/OUT_P1") (class "Default")
      (node (ref "C17") (pin "2") (pinfunction "2_2") (pintype "passive"))
      (node (ref "R11") (pin "1") (pinfunction "1_1") (pintype "passive"))
      (node (ref "TP9") (pin "1") (pinfunction "G9_1") (pintype "passive"))
      (node (ref "X2") (pin "5") (pinfunction "5_5") (pintype "passive"))
    )
    (net (code "18") (name "/RX") (class "Default")
      (node (ref "J8") (pin "5") (pinfunction "5_5") (pintype "passive"))
      (node (ref "R37") (pin "1") (pinfunction "1_1") (pintype "passive"))
      (node (ref "TP28") (pin "1") (pinfunction "G9_1") (pintype "passive"))
      (node (ref "U10") (pin "6") (pinfunction "VOD_6") (pintype "tri_state"))
      (node (ref "U6") (pin "1") (pinfunction "PB7/PB8_1") (pintype "bidirectional"))
    )
    (net (code "19") (name "/SCL") (class "Default")
      (node (ref "R4") (pin "1") (pinfunction "1_1") (pintype "passive"))
      (node (ref "R7") (pin "1") (pinfunction "1_1") (pintype "passive"))
      (node (ref "U6") (pin "16") (pinfunction "PA11[PA9]_16") (pintype "bidirectional"))
      (node (ref "VD1") (pin "2") (pinfunction "C_2") (pintype "passive"))
    )
    (net (code "20") (name "/SDA") (class "Default")
      (node (ref "R10") (pin "1") (pinfunction "1_1") (pintype "passive"))
      (node (ref "R5") (pin "1") (pinfunction "1_1") (pintype "passive"))
      (node (ref "U6") (pin "17") (pinfunction "PA12[PA10]_17") (pintype "bidirectional"))
      (node (ref "VD2") (pin "2") (pinfunction "C_2") (pintype "passive"))
    )
    (net (code "21") (name "/SWCLC") (class "Default")
      (node (ref "J8") (pin "3") (pinfunction "3_3") (pintype "passive"))
      (node (ref "R30") (pin "1") (pinfunction "1_1") (pintype "passive"))
      (node (ref "U6") (pin "19") (pinfunction "PA15/PA14-BOOT0_19") (pintype "bidirectional"))
    )
    (net (code "22") (name "/SWDIO") (class "Default")
      (node (ref "J8") (pin "2") (pinfunction "2_2") (pintype "passive"))
      (node (ref "U6") (pin "18") (pinfunction "PA13_18") (pintype "bidirectional"))
    )
    (net (code "23") (name "/TX") (class "Default")
      (node (ref "J8") (pin "4") (pinfunction "4_4") (pintype "passive"))
      (node (ref "R40") (pin "1") (pinfunction "1_1") (pintype "passive"))
      (node (ref "TP26") (pin "1") (pinfunction "G9_1") (pintype "passive"))
      (node (ref "U10") (pin "4") (pinfunction "VIB_4") (pintype "input"))
      (node (ref "U6") (pin "20") (pinfunction "PB3/PB4/PB5/PB6_20") (pintype "bidirectional"))
    )
    (net (code "24") (name "GND_2") (class "Default")
      (node (ref "C36") (pin "2") (pinfunction "2_2") (pintype "passive"))
      (node (ref "P2") (pin "2") (pinfunction "2_2") (pintype "passive"))
      (node (ref "R46") (pin "1") (pinfunction "1_1") (pintype "passive"))
      (node (ref "R49") (pin "1") (pinfunction "1_1") (pintype "passive"))
      (node (ref "TP30") (pin "1") (pinfunction "G9_1") (pintype "passive"))
      (node (ref "U10") (pin "15") (pinfunction "GND2_15") (pintype "power_in"))
      (node (ref "U10") (pin "9") (pinfunction "GND2_9") (pintype "power_in"))
      (node (ref "U8") (pin "3") (pinfunction "0V_3") (pintype "power_in"))
      (node (ref "U9") (pin "5") (pinfunction "GND_5") (pintype "power_in"))
      (node (ref "ZD2") (pin "1") (pinfunction "A_1") (pintype "passive"))
      (node (ref "ZD3") (pin "1") (pinfunction "A_1") (pintype "passive"))
    )
    (net (code "25") (name "GND_III") (class "Default")
      (node (ref "C1") (pin "1") (pinfunction "1_1") (pintype "passive"))
      (node (ref "C10") (pin "2") (pinfunction "-_2") (pintype "passive"))
      (node (ref "C12") (pin "2") (pinfunction "-_2") (pintype "passive"))
      (node (ref "C13") (pin "1") (pinfunction "1_1") (pintype "passive"))
      (node (ref "C18") (pin "1") (pinfunction "1_1") (pintype "passive"))
      (node (ref "C19") (pin "1") (pinfunction "1_1") (pintype "passive"))
      (node (ref "C2") (pin "1") (pinfunction "1_1") (pintype "passive"))
      (node (ref "C21") (pin "1") (pinfunction "1_1") (pintype "passive"))
      (node (ref "C25") (pin "1") (pinfunction "1_1") (pintype "passive"))
      (node (ref "C26") (pin "1") (pinfunction "1_1") (pintype "passive"))
      (node (ref "C27") (pin "2") (pinfunction "2_2") (pintype "passive"))
      (node (ref "C3") (pin "2") (pinfunction "-_2") (pintype "passive"))
      (node (ref "C30") (pin "1") (pinfunction "1_1") (pintype "passive"))
      (node (ref "C31") (pin "1") (pinfunction "1_1") (pintype "passive"))
      (node (ref "C32") (pin "2") (pinfunction "2_2") (pintype "passive"))
      (node (ref "C34") (pin "1") (pinfunction "1_1") (pintype "passive"))
      (node (ref "C37") (pin "1") (pinfunction "1_1") (pintype "passive"))
      (node (ref "C38") (pin "1") (pinfunction "1_1") (pintype "passive"))
      (node (ref "C39") (pin "1") (pinfunction "1_1") (pintype "passive"))
      (node (ref "C4") (pin "2") (pinfunction "-_2") (pintype "passive"))
      (node (ref "C6") (pin "1") (pinfunction "1_1") (pintype "passive"))
      (node (ref "C7") (pin "1") (pinfunction "1_1") (pintype "passive"))
      (node (ref "C8") (pin "1") (pinfunction "1_1") (pintype "passive"))
      (node (ref "D10") (pin "2") (pinfunction "A_2") (pintype "passive"))
      (node (ref "D11") (pin "2") (pinfunction "A_2") (pintype "passive"))
      (node (ref "D12") (pin "2") (pinfunction "A_2") (pintype "passive"))
      (node (ref "D13") (pin "2") (pinfunction "K_2") (pintype "passive"))
      (node (ref "D2") (pin "2") (pinfunction "A_2") (pintype "passive"))
      (node (ref "D3") (pin "2") (pinfunction "K_2") (pintype "passive"))
      (node (ref "D4") (pin "2") (pinfunction "K_2") (pintype "passive"))
      (node (ref "D6") (pin "2") (pinfunction "A_2") (pintype "passive"))
      (node (ref "J11") (pin "2") (pinfunction "2_2") (pintype "passive"))
      (node (ref "J12") (pin "2") (pinfunction "2_2") (pintype "passive"))
      (node (ref "J13") (pin "2") (pinfunction "2_2") (pintype "passive"))
      (node (ref "J3") (pin "1") (pinfunction "1_1") (pintype "passive"))
      (node (ref "J8") (pin "6") (pinfunction "6_6") (pintype "passive"))
      (node (ref "J9") (pin "2") (pinfunction "2_2") (pintype "passive"))
      (node (ref "P1") (pin "1") (pinfunction "1_1") (pintype "passive"))
      (node (ref "R1") (pin "2") (pinfunction "2_2") (pintype "passive"))
      (node (ref "R16") (pin "2") (pinfunction "2_2") (pintype "passive"))
      (node (ref "R2") (pin "1") (pinfunction "1_1") (pintype "passive"))
      (node (ref "R20") (pin "1") (pinfunction "1_1") (pintype "passive"))
      (node (ref "R30") (pin "2") (pinfunction "2_2") (pintype "passive"))
      (node (ref "R32") (pin "1") (pinfunction "1_1") (pintype "passive"))
      (node (ref "R34") (pin "1") (pinfunction "1_1") (pintype "passive"))
      (node (ref "R48") (pin "1") (pinfunction "1_1") (pintype "passive"))
      (node (ref "TP21") (pin "1") (pinfunction "G9_1") (pintype "passive"))
      (node (ref "TP4") (pin "1") (pinfunction "G9_1") (pintype "passive"))
      (node (ref "U10") (pin "2") (pinfunction "GND1_2") (pintype "power_in"))
      (node (ref "U10") (pin "8") (pinfunction "GND1_8") (pintype "power_in"))
      (node (ref "U2") (pin "1") (pinfunction "Ground_1") (pintype "power_in"))
      (node (ref "U5") (pin "2") (pinfunction "VSS_2") (pintype "power_in"))
      (node (ref "U6") (pin "5") (pinfunction "VSS/VSSA_5") (pintype "power_in"))
      (node (ref "U7") (pin "4") (pinfunction "GND_4") (pintype "power_in"))
      (node (ref "U8") (pin "1") (pinfunction "GND_1") (pintype "power_in"))
      (node (ref "VD1") (pin "1") (pinfunction "A_1") (pintype "passive"))
      (node (ref "VD2") (pin "1") (pinfunction "A_1") (pintype "passive"))
      (node (ref "X1") (pin "1") (pinfunction "1_1") (pintype "passive"))
      (node (ref "X1") (pin "2") (pinfunction "2_2") (pintype "passive"))
      (node (ref "X1") (pin "4") (pinfunction "4_4") (pintype "passive"))
      (node (ref "X2") (pin "1") (pinfunction "1_1") (pintype "passive"))
      (node (ref "X2") (pin "2") (pinfunction "2_2") (pintype "passive"))
      (node (ref "X3") (pin "2") (pinfunction "2_2") (pintype "passive"))
      (node (ref "X3") (pin "3") (pinfunction "3_3") (pintype "passive"))
    )
    (net (code "26") (name "Net-(C18-Pad2)") (class "Default")
      (node (ref "C18") (pin "2") (pinfunction "2_2") (pintype "passive"))
      (node (ref "R12") (pin "1") (pinfunction "1_1") (pintype "passive"))
      (node (ref "R13") (pin "2") (pinfunction "2_2") (pintype "passive"))
    )
    (net (code "27") (name "Net-(D1-A)") (class "Default")
      (node (ref "D1") (pin "1") (pinfunction "A_1") (pintype "passive"))
      (node (ref "R25") (pin "1") (pinfunction "1_1") (pintype "passive"))
    )
    (net (code "28") (name "Net-(D2-C)") (class "Default")
      (node (ref "D2") (pin "1") (pinfunction "C_1") (pintype "passive"))
      (node (ref "L2") (pin "1") (pinfunction "1_1") (pintype "passive"))
      (node (ref "TP18") (pin "1") (pinfunction "G9_1") (pintype "passive"))
      (node (ref "U7") (pin "2") (pinfunction "SWE_2") (pintype "open_emitter"))
    )
    (net (code "29") (name "Net-(D3-A)") (class "Default")
      (node (ref "D3") (pin "1") (pinfunction "A_1") (pintype "passive"))
      (node (ref "R27") (pin "2") (pinfunction "2_2") (pintype "passive"))
    )
    (net (code "30") (name "Net-(D4-A)") (class "Default")
      (node (ref "D4") (pin "1") (pinfunction "A_1") (pintype "passive"))
      (node (ref "R31") (pin "2") (pinfunction "2_2") (pintype "passive"))
    )
    (net (code "31") (name "Net-(D13-A)") (class "Default")
      (node (ref "D13") (pin "1") (pinfunction "A_1") (pintype "passive"))
      (node (ref "R47") (pin "1") (pinfunction "1_1") (pintype "passive"))
    )
    (net (code "32") (name "Net-(J3-Pad3)") (class "Default")
      (node (ref "J3") (pin "3") (pinfunction "3_3") (pintype "passive"))
      (node (ref "R7") (pin "2") (pinfunction "2_2") (pintype "passive"))
    )
    (net (code "33") (name "Net-(J3-Pad4)") (class "Default")
      (node (ref "J3") (pin "4") (pinfunction "4_4") (pintype "passive"))
      (node (ref "R10") (pin "2") (pinfunction "2_2") (pintype "passive"))
    )
    (net (code "34") (name "Net-(TP10-G9)") (class "Default")
      (node (ref "C16") (pin "2") (pinfunction "2_2") (pintype "passive"))
      (node (ref "C21") (pin "2") (pinfunction "2_2") (pintype "passive"))
      (node (ref "R11") (pin "2") (pinfunction "2_2") (pintype "passive"))
      (node (ref "R20") (pin "2") (pinfunction "2_2") (pintype "passive"))
      (node (ref "TP10") (pin "1") (pinfunction "G9_1") (pintype "passive"))
      (node (ref "U5") (pin "3") (pinfunction "VIN+_3") (pintype "input"))
    )
    (net (code "35") (name "Net-(TP11-G9)") (class "Default")
      (node (ref "C19") (pin "2") (pinfunction "2_2") (pintype "passive"))
      (node (ref "R13") (pin "1") (pinfunction "1_1") (pintype "passive"))
      (node (ref "R14") (pin "2") (pinfunction "2_2") (pintype "passive"))
      (node (ref "R16") (pin "1") (pinfunction "1_1") (pintype "passive"))
      (node (ref "TP11") (pin "1") (pinfunction "G9_1") (pintype "passive"))
    )
    (net (code "36") (name "Net-(TP12-G9)") (class "Default")
      (node (ref "C22") (pin "2") (pinfunction "2_2") (pintype "passive"))
      (node (ref "R12") (pin "2") (pinfunction "2_2") (pintype "passive"))
      (node (ref "R21") (pin "2") (pinfunction "2_2") (pintype "passive"))
      (node (ref "TP12") (pin "1") (pinfunction "G9_1") (pintype "passive"))
      (node (ref "U5") (pin "1") (pinfunction "VOUT_1") (pintype "output"))
    )
    (net (code "37") (name "Net-(TP14-G9)") (class "Default")
      (node (ref "C16") (pin "1") (pinfunction "1_1") (pintype "passive"))
      (node (ref "C22") (pin "1") (pinfunction "1_1") (pintype "passive"))
      (node (ref "R15") (pin "2") (pinfunction "2_2") (pintype "passive"))
      (node (ref "R21") (pin "1") (pinfunction "1_1") (pintype "passive"))
      (node (ref "TP14") (pin "1") (pinfunction "G9_1") (pintype "passive"))
      (node (ref "U5") (pin "4") (pinfunction "VIN-_4") (pintype "input"))
    )
    (net (code "38") (name "Net-(TP19-G9)") (class "Default")
      (node (ref "C30") (pin "2") (pinfunction "2_2") (pintype "passive"))
      (node (ref "JE1") (pin "2") (pinfunction "2_2") (pintype "passive"))
      (node (ref "L3") (pin "2") (pinfunction "2_2") (pintype "passive"))
      (node (ref "TP19") (pin "1") (pinfunction "G9_1") (pintype "passive"))
    )
    (net (code "39") (name "Net-(TP24-G9)") (class "Default")
      (node (ref "R38") (pin "1") (pinfunction "1_1") (pintype "passive"))
      (node (ref "R41") (pin "1") (pinfunction "1_1") (pintype "passive"))
      (node (ref "TP24") (pin "1") (pinfunction "G9_1") (pintype "passive"))
      (node (ref "U9") (pin "4") (pinfunction "DI_4") (pintype "input"))
    )
    (net (code "40") (name "Net-(TP27-G9)") (class "Default")
      (node (ref "R46") (pin "2") (pinfunction "2_2") (pintype "passive"))
      (node (ref "TP27") (pin "1") (pinfunction "G9_1") (pintype "passive"))
      (node (ref "U10") (pin "12") (pinfunction "VOC_12") (pintype "tri_state"))
      (node (ref "U9") (pin "2") (pinfunction "~{RE}_2") (pintype "input"))
      (node (ref "U9") (pin "3") (pinfunction "DE_3") (pintype "input"))
    )
    (net (code "41") (name "Net-(TP29-G9)") (class "Default")
      (node (ref "R39") (pin "1") (pinfunction "1_1") (pintype "passive"))
      (node (ref "R45") (pin "1") (pinfunction "1_1") (pintype "passive"))
      (node (ref "TP29") (pin "1") (pinfunction "G9_1") (pintype "passive"))
      (node (ref "U9") (pin "1") (pinfunction "RO_1") (pintype "output"))
    )
    (net (code "42") (name "Net-(U6-PA7)") (class "Default")
      (node (ref "R27") (pin "1") (pinfunction "1_1") (pintype "passive"))
      (node (ref "U6") (pin "14") (pinfunction "PA7_14") (pintype "bidirectional"))
    )
    (net (code "43") (name "Net-(U6-PC15-OSC32_OUT)") (class "Default")
      (node (ref "R31") (pin "1") (pinfunction "1_1") (pintype "passive"))
      (node (ref "U6") (pin "3") (pinfunction "PC15-OSC32_OUT_3") (pintype "bidirectional"))
    )
    (net (code "44") (name "Net-(U6-~{RST})") (class "Default")
      (node (ref "C26") (pin "2") (pinfunction "2_2") (pintype "passive"))
      (node (ref "R26") (pin "2") (pinfunction "2_2") (pintype "passive"))
      (node (ref "U6") (pin "6") (pinfunction "~{RST}_6") (pintype "input"))
    )
    (net (code "45") (name "Net-(U7-CII)") (class "Default")
      (node (ref "R33") (pin "2") (pinfunction "2_2") (pintype "passive"))
      (node (ref "R34") (pin "2") (pinfunction "2_2") (pintype "passive"))
      (node (ref "U7") (pin "5") (pinfunction "CII_5") (pintype "input"))
    )
    (net (code "46") (name "Net-(U7-DRC)") (class "Default")
      (node (ref "R28") (pin "2") (pinfunction "2_2") (pintype "passive"))
      (node (ref "U7") (pin "1") (pinfunction "SWC_1") (pintype "open_collector"))
      (node (ref "U7") (pin "7") (pinfunction "IPK_7") (pintype "passive"))
      (node (ref "U7") (pin "8") (pinfunction "DRC_8") (pintype "open_collector"))
    )
    (net (code "47") (name "Net-(U7-TC)") (class "Default")
      (node (ref "C27") (pin "1") (pinfunction "1_1") (pintype "passive"))
      (node (ref "U7") (pin "3") (pinfunction "TC_3") (pintype "passive"))
    )
    (net (code "48") (name "Net-(U9-A)") (class "Default")
      (node (ref "P2") (pin "3") (pinfunction "3_3") (pintype "passive"))
      (node (ref "R36") (pin "1") (pinfunction "1_1") (pintype "passive"))
      (node (ref "U9") (pin "6") (pinfunction "A_6") (pintype "bidirectional"))
      (node (ref "ZD1") (pin "2") (pinfunction "A_2") (pintype "passive"))
      (node (ref "ZD2") (pin "2") (pinfunction "A_2") (pintype "passive"))
    )
    (net (code "49") (name "Net-(U9-B)") (class "Default")
      (node (ref "P2") (pin "1") (pinfunction "1_1") (pintype "passive"))
      (node (ref "R49") (pin "2") (pinfunction "2_2") (pintype "passive"))
      (node (ref "U9") (pin "7") (pinfunction "B_7") (pintype "bidirectional"))
      (node (ref "ZD1") (pin "1") (pinfunction "A_1") (pintype "passive"))
      (node (ref "ZD3") (pin "2") (pinfunction "A_2") (pintype "passive"))
    )
    (net (code "50") (name "Net-(U10-VID)") (class "Default")
      (node (ref "R45") (pin "2") (pinfunction "2_2") (pintype "passive"))
      (node (ref "U10") (pin "11") (pinfunction "VID_11") (pintype "input"))
    )
    (net (code "51") (name "Net-(U10-VOB)") (class "Default")
      (node (ref "R41") (pin "2") (pinfunction "2_2") (pintype "passive"))
      (node (ref "U10") (pin "13") (pinfunction "VOB_13") (pintype "tri_state"))
    )
    (net (code "52") (name "VCC") (class "Default")
      (node (ref "C12") (pin "1") (pinfunction "+_1") (pintype "passive"))
      (node (ref "C32") (pin "1") (pinfunction "1_1") (pintype "passive"))
      (node (ref "P1") (pin "2") (pinfunction "2_2") (pintype "passive"))
      (node (ref "R28") (pin "1") (pinfunction "1_1") (pintype "passive"))
      (node (ref "U7") (pin "6") (pinfunction "VCC_6") (pintype "power_in"))
      (node (ref "X3") (pin "4") (pinfunction "4_4") (pintype "passive"))
      (node (ref "X3") (pin "5") (pinfunction "5_5") (pintype "passive"))
    )
    (net (code "53") (name "unconnected-(DD1-GND-Pad1)") (class "Default")
      (node (ref "DD1") (pin "1") (pinfunction "GND_1") (pintype "passive"))
    )
    (net (code "54") (name "unconnected-(DD1-SCL-Pad3)") (class "Default")
      (node (ref "DD1") (pin "3") (pinfunction "SCL_3") (pintype "passive"))
    )
    (net (code "55") (name "unconnected-(DD1-SDA-Pad4)") (class "Default")
      (node (ref "DD1") (pin "4") (pinfunction "SDA_4") (pintype "passive"))
    )
    (net (code "56") (name "unconnected-(DD1-VCC-Pad2)") (class "Default")
      (node (ref "DD1") (pin "2") (pinfunction "VCC_2") (pintype "passive"))
    )
    (net (code "57") (name "unconnected-(U10-VIA-Pad3)") (class "Default")
      (node (ref "U10") (pin "3") (pinfunction "VIA_3") (pintype "input"))
    )
    (net (code "58") (name "unconnected-(U10-VOA-Pad14)") (class "Default")
      (node (ref "U10") (pin "14") (pinfunction "VOA_14") (pintype "tri_state"))
    )
  )
)
